# Pressure_sensor_-_SCP1000-D01.net
KiCad netlist of a schematic drawn in Altium Designer
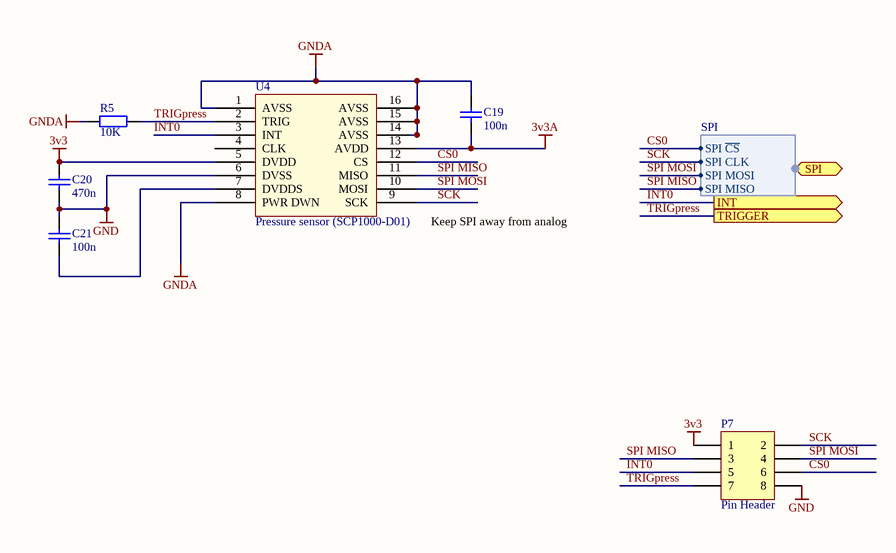
[diagram p0: Pressure sensor - SCP1000-D01.SchDoc]

(export (version "E")
  (design (tool "Eeschema 10.0.6"))
  (components
    (comp (ref "C19")
      (value "100n")
      (footprint "C0805")
      (fields (field (name "TOLERANCE") "0.1") (field (name "AUTHOR") "Willy Pietersz"))
      (libsource (lib "OurDb") (part "cap_NonPolar"))
    )
    (comp (ref "C20")
      (value "470n")
      (footprint "C0805")
      (fields (field (name "TOLERANCE") "0.1") (field (name "AUTHOR") "Willy Pietersz"))
      (libsource (lib "OurDb") (part "cap_NonPolar"))
    )
    (comp (ref "C21")
      (value "100n")
      (footprint "C0805")
      (fields (field (name "TOLERANCE") "0.1") (field (name "AUTHOR") "Willy Pietersz"))
      (libsource (lib "OurDb") (part "cap_NonPolar"))
    )
    (comp (ref "P7")
      (value "Pin Header")
      (footprint "PH2x4_2.54")
      (description "Header, 4-Pin, Dual row")
      (fields (field (name "PART NUMBER") "PH2x4") (field (name "AUTHOR") "Willy Pietersz"))
      (libsource (lib "OurDb") (part "Con2x4"))
    )
    (comp (ref "R5")
      (value "10K")
      (footprint "R0805")
      (description "Resistor")
      (fields
        (field (name "POWER") "0.25W")
        (field (name "TOLERANCE") "0.05")
        (field (name "PUBLISHER") "Altium Limited")
        (field (name "AUTHOR") "Willy Pietersz")
      )
      (libsource (lib "OurDb") (part "RESISTOR"))
    )
    (comp (ref "U4")
      (value "Pressure sensor (SCP1000-D01)")
      (footprint "SCP1000-D01")
      (fields (field (name "PART NUMBER") "SCP1000-D01"))
      (libsource (lib "OurDb") (part "SCP1000-D01"))
    )
  )
  (nets
    (net (code "2") (name "/CS0") (class "Default")
      (node (ref "P7") (pin "6") (pinfunction "6_6") (pintype "passive"))
      (node (ref "U4") (pin "12") (pinfunction "CS_12") (pintype "passive"))
    )
    (net (code "3") (name "/INT0") (class "Default")
      (node (ref "P7") (pin "5") (pinfunction "5_5") (pintype "passive"))
      (node (ref "U4") (pin "3") (pinfunction "INT_3") (pintype "passive"))
    )
    (net (code "4") (name "/SCK") (class "Default")
      (node (ref "P7") (pin "2") (pinfunction "2_2") (pintype "passive"))
      (node (ref "U4") (pin "9") (pinfunction "SCK_9") (pintype "passive"))
    )
    (net (code "5") (name "/SPI MISO") (class "Default")
      (node (ref "P7") (pin "3") (pinfunction "3_3") (pintype "passive"))
      (node (ref "U4") (pin "11") (pinfunction "MISO_11") (pintype "passive"))
    )
    (net (code "6") (name "/SPI MOSI") (class "Default")
      (node (ref "P7") (pin "4") (pinfunction "4_4") (pintype "passive"))
      (node (ref "U4") (pin "10") (pinfunction "MOSI_10") (pintype "passive"))
    )
    (net (code "7") (name "/TRIGpress") (class "Default")
      (node (ref "P7") (pin "7") (pinfunction "7_7") (pintype "passive"))
      (node (ref "R5") (pin "2") (pinfunction "2_2") (pintype "passive"))
      (node (ref "U4") (pin "2") (pinfunction "TRIG_2") (pintype "passive"))
    )
    (net (code "9") (name "3v3") (class "Default")
      (node (ref "C20") (pin "2") (pinfunction "2_2") (pintype "passive"))
      (node (ref "P7") (pin "1") (pinfunction "1_1") (pintype "passive"))
      (node (ref "U4") (pin "5") (pinfunction "DVDD_5") (pintype "passive"))
    )
    (net (code "10") (name "3v3A") (class "Default")
      (node (ref "C19") (pin "1") (pinfunction "1_1") (pintype "passive"))
      (node (ref "U4") (pin "13") (pinfunction "AVDD_13") (pintype "passive"))
    )
    (net (code "11") (name "GND") (class "Default")
      (node (ref "C20") (pin "1") (pinfunction "1_1") (pintype "passive"))
      (node (ref "C21") (pin "2") (pinfunction "2_2") (pintype "passive"))
      (node (ref "P7") (pin "8") (pinfunction "8_8") (pintype "passive"))
      (node (ref "U4") (pin "6") (pinfunction "DVSS_6") (pintype "passive"))
    )
    (net (code "12") (name "GNDA") (class "Default")
      (node (ref "C19") (pin "2") (pinfunction "2_2") (pintype "passive"))
      (node (ref "R5") (pin "1") (pinfunction "1_1") (pintype "passive"))
      (node (ref "U4") (pin "1") (pinfunction "AVSS_1") (pintype "passive"))
      (node (ref "U4") (pin "14") (pinfunction "AVSS_14") (pintype "passive"))
      (node (ref "U4") (pin "15") (pinfunction "AVSS_15") (pintype "passive"))
      (node (ref "U4") (pin "16") (pinfunction "AVSS_16") (pintype "passive"))
      (node (ref "U4") (pin "8") (pinfunction "PWR_DWN_8") (pintype "passive"))
    )
    (net (code "13") (name "Net-(U4-DVDDS)") (class "Default")
      (node (ref "C21") (pin "1") (pinfunction "1_1") (pintype "passive"))
      (node (ref "U4") (pin "7") (pinfunction "DVDDS_7") (pintype "passive"))
    )
    (net (code "14") (name "unconnected-(U4-CLK-Pad4)") (class "Default")
      (node (ref "U4") (pin "4") (pinfunction "CLK_4") (pintype "passive"))
    )
  )
)
